# RJ45_Ethernet.net
KiCad netlist of a schematic drawn in Altium Designer
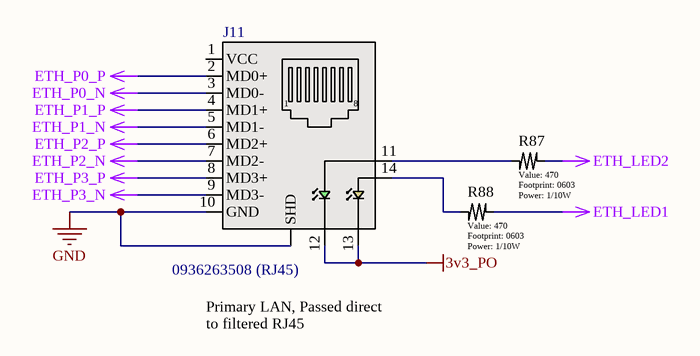
[diagram p0: RJ45_Ethernet.SchDoc]

(export (version "E")
  (design (tool "Eeschema 10.0.6"))
  (components
    (comp (ref "J11")
      (value "0936263508 (RJ45)")
      (footprint "0936263508")
      (description "1 Port RJ45Through Hole 10/100/1000 Base-T, AutoMDIX")
      (libsource (lib "Connectors") (part "0936263508  (RJ45)"))
    )
    (comp (ref "R87")
      (value "470")
      (footprint "0603")
      (fields
        (field (name "TOLERANCE") "1%")
        (field (name "POWER") "1/10W")
        (field (name "Comment") "Generic Resistor")
      )
      (libsource (lib "Resistors") (part "Generic Resistor"))
    )
    (comp (ref "R88")
      (value "470")
      (footprint "0603")
      (fields
        (field (name "TOLERANCE") "1%")
        (field (name "POWER") "1/10W")
        (field (name "Comment") "Generic Resistor")
      )
      (libsource (lib "Resistors") (part "Generic Resistor"))
    )
  )
  (nets
    (net (code "1") (name "3v3_PO") (class "Default")
      (node (ref "J11") (pin "12") (pinfunction "Cathode_12") (pintype "passive"))
      (node (ref "J11") (pin "13") (pinfunction "Cathode_13") (pintype "passive"))
    )
    (net (code "2") (name "ETH_LED1") (class "Default")
      (node (ref "R88") (pin "2") (pinfunction "2_2") (pintype "passive"))
    )
    (net (code "3") (name "ETH_LED2") (class "Default")
      (node (ref "R87") (pin "2") (pinfunction "2_2") (pintype "passive"))
    )
    (net (code "4") (name "ETH_P0_N") (class "Default")
      (node (ref "J11") (pin "3") (pinfunction "MD0-_3") (pintype "passive"))
    )
    (net (code "5") (name "ETH_P0_P") (class "Default")
      (node (ref "J11") (pin "2") (pinfunction "MD0+_2") (pintype "passive"))
    )
    (net (code "6") (name "ETH_P1_N") (class "Default")
      (node (ref "J11") (pin "5") (pinfunction "MD1-_5") (pintype "passive"))
    )
    (net (code "7") (name "ETH_P1_P") (class "Default")
      (node (ref "J11") (pin "4") (pinfunction "MD1+_4") (pintype "passive"))
    )
    (net (code "8") (name "ETH_P2_N") (class "Default")
      (node (ref "J11") (pin "7") (pinfunction "MD2-_7") (pintype "passive"))
    )
    (net (code "9") (name "ETH_P2_P") (class "Default")
      (node (ref "J11") (pin "6") (pinfunction "MD2+_6") (pintype "passive"))
    )
    (net (code "10") (name "ETH_P3_N") (class "Default")
      (node (ref "J11") (pin "9") (pinfunction "MD3-_9") (pintype "passive"))
    )
    (net (code "11") (name "ETH_P3_P") (class "Default")
      (node (ref "J11") (pin "8") (pinfunction "MD3+_8") (pintype "passive"))
    )
    (net (code "12") (name "GND") (class "Default")
      (node (ref "J11") (pin "10") (pinfunction "GND_10") (pintype "passive"))
      (node (ref "J11") (pin "SHD") (pinfunction "SHD_SHD") (pintype "passive"))
    )
    (net (code "13") (name "Net-(J11-Anode-Pad11)") (class "Default")
      (node (ref "J11") (pin "11") (pinfunction "Anode_11") (pintype "passive"))
      (node (ref "R87") (pin "1") (pinfunction "1_1") (pintype "passive"))
    )
    (net (code "14") (name "Net-(J11-Anode-Pad14)") (class "Default")
      (node (ref "J11") (pin "14") (pinfunction "Anode_14") (pintype "passive"))
      (node (ref "R88") (pin "1") (pinfunction "1_1") (pintype "passive"))
    )
    (net (code "15") (name "unconnected-(J11-VCC-Pad1)") (class "Default")
      (node (ref "J11") (pin "1") (pinfunction "VCC_1") (pintype "passive"))
    )
  )
)
